# Dual_Motor_Driver.net
KiCad netlist of a schematic drawn in EAGLE
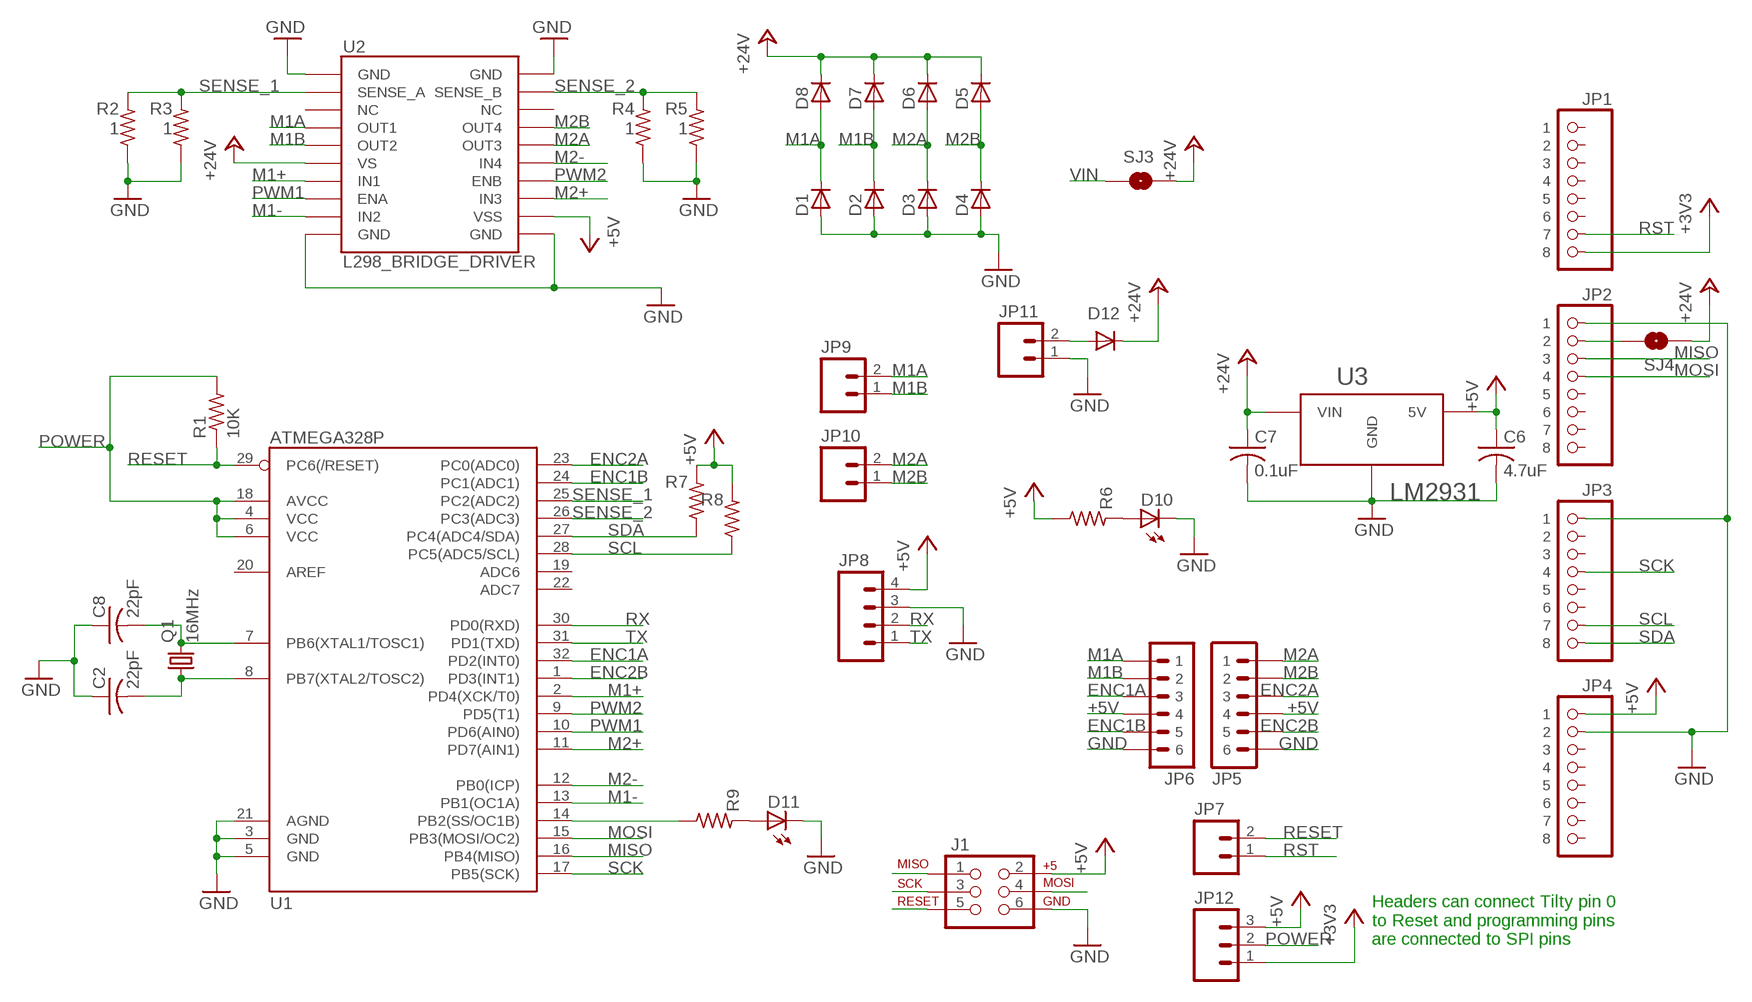
[diagram p0: schematic, sheet 1]

(export (version "E")
  (design (tool "Eeschema 10.0.6"))
  (components
    (comp (ref "C2")
      (value "22pF")
      (footprint "eagle-import:C0603")
      (libsource (lib "eagle-import") (part "C-USC0603"))
    )
    (comp (ref "C6")
      (value "4.7uF")
      (footprint "eagle-import:C0603")
      (libsource (lib "eagle-import") (part "C-USC0603"))
    )
    (comp (ref "C7")
      (value "0.1uF")
      (footprint "eagle-import:C0603")
      (libsource (lib "eagle-import") (part "C-USC0603"))
    )
    (comp (ref "C8")
      (value "22pF")
      (footprint "eagle-import:C0603")
      (libsource (lib "eagle-import") (part "C-USC0603"))
    )
    (comp (ref "D1")
      (value "D-SOD123")
      (footprint "eagle-import:SOD123")
      (fields (field (name "PART#") "CDBW140-G"))
      (libsource (lib "eagle-import") (part "D-SOD123"))
    )
    (comp (ref "D2")
      (value "D-SOD123")
      (footprint "eagle-import:SOD123")
      (fields (field (name "PART#") "CDBW140-G"))
      (libsource (lib "eagle-import") (part "D-SOD123"))
    )
    (comp (ref "D3")
      (value "D-SOD123")
      (footprint "eagle-import:SOD123")
      (fields (field (name "PART#") "CDBW140-G"))
      (libsource (lib "eagle-import") (part "D-SOD123"))
    )
    (comp (ref "D4")
      (value "D-SOD123")
      (footprint "eagle-import:SOD123")
      (fields (field (name "PART#") "CDBW140-G"))
      (libsource (lib "eagle-import") (part "D-SOD123"))
    )
    (comp (ref "D5")
      (value "D-SOD123")
      (footprint "eagle-import:SOD123")
      (fields (field (name "PART#") "CDBW140-G"))
      (libsource (lib "eagle-import") (part "D-SOD123"))
    )
    (comp (ref "D6")
      (value "D-SOD123")
      (footprint "eagle-import:SOD123")
      (fields (field (name "PART#") "CDBW140-G"))
      (libsource (lib "eagle-import") (part "D-SOD123"))
    )
    (comp (ref "D7")
      (value "D-SOD123")
      (footprint "eagle-import:SOD123")
      (fields (field (name "PART#") "CDBW140-G"))
      (libsource (lib "eagle-import") (part "D-SOD123"))
    )
    (comp (ref "D8")
      (value "D-SOD123")
      (footprint "eagle-import:SOD123")
      (fields (field (name "PART#") "CDBW140-G"))
      (libsource (lib "eagle-import") (part "D-SOD123"))
    )
    (comp (ref "D10")
      (value "LED-GREENLED-0805_NO_SILK")
      (footprint "eagle-import:LED-0805")
      (libsource (lib "eagle-import") (part "LED-GREENLED-0805_NO_SILK"))
    )
    (comp (ref "D11")
      (value "LED-GREENLED-0805_NO_SILK")
      (footprint "eagle-import:LED-0805")
      (libsource (lib "eagle-import") (part "LED-GREENLED-0805_NO_SILK"))
    )
    (comp (ref "D12")
      (value "DIODESMB")
      (footprint "eagle-import:SMB-DIODE")
      (libsource (lib "eagle-import") (part "DIODESMB"))
    )
    (comp (ref "J1")
      (value "AVR_SPI_PRG_62X3_LOCK")
      (footprint "eagle-import:2X3_LOCK")
      (libsource (lib "eagle-import") (part "AVR_SPI_PRG_62X3_LOCK"))
    )
    (comp (ref "JP1")
      (value "8-PIN_HEADER")
      (footprint "eagle-import:8-PIN_RECEPTACLE_LOCK_NO-SS")
      (libsource (lib "eagle-import") (part "8-PIN_HEADER"))
    )
    (comp (ref "JP2")
      (value "8-PIN_HEADER")
      (footprint "eagle-import:8-PIN_RECEPTACLE_LOCK_NO-SS")
      (libsource (lib "eagle-import") (part "8-PIN_HEADER"))
    )
    (comp (ref "JP3")
      (value "8-PIN_HEADER")
      (footprint "eagle-import:8-PIN_RECEPTACLE_LOCK_NO-SS")
      (libsource (lib "eagle-import") (part "8-PIN_HEADER"))
    )
    (comp (ref "JP4")
      (value "8-PIN_HEADER")
      (footprint "eagle-import:8-PIN_RECEPTACLE_LOCK_NO-SS")
      (libsource (lib "eagle-import") (part "8-PIN_HEADER"))
    )
    (comp (ref "JP5")
      (value "6PIN-SH_RIGHT_ANGLE")
      (footprint "eagle-import:6PIN-SH_SERIES_RA")
      (fields (field (name "PART#") "SM06B-SRSS-TB(LF)(SN)"))
      (libsource (lib "eagle-import") (part "6PIN-SH_RIGHT_ANGLE"))
    )
    (comp (ref "JP6")
      (value "6PIN-SH_RIGHT_ANGLE")
      (footprint "eagle-import:6PIN-SH_SERIES_RA")
      (fields (field (name "PART#") "SM06B-SRSS-TB(LF)(SN)"))
      (libsource (lib "eagle-import") (part "6PIN-SH_RIGHT_ANGLE"))
    )
    (comp (ref "JP7")
      (value "M02PTH")
      (footprint "eagle-import:1X02")
      (libsource (lib "eagle-import") (part "M02PTH"))
    )
    (comp (ref "JP8")
      (value "M04PTH")
      (footprint "eagle-import:1X04")
      (libsource (lib "eagle-import") (part "M04PTH"))
    )
    (comp (ref "JP9")
      (value "M02PTH")
      (footprint "eagle-import:1X02")
      (libsource (lib "eagle-import") (part "M02PTH"))
    )
    (comp (ref "JP10")
      (value "M02PTH")
      (footprint "eagle-import:1X02")
      (libsource (lib "eagle-import") (part "M02PTH"))
    )
    (comp (ref "JP11")
      (value "M02PTH")
      (footprint "eagle-import:1X02")
      (libsource (lib "eagle-import") (part "M02PTH"))
    )
    (comp (ref "JP12")
      (value "M03PTH")
      (footprint "eagle-import:1X03")
      (libsource (lib "eagle-import") (part "M03PTH"))
    )
    (comp (ref "Q1")
      (value "16MHz")
      (footprint "eagle-import:CTS406")
      (fields (field (name "PART#") "406C35D16M00000"))
      (libsource (lib "eagle-import") (part "CRYSTALCTS406"))
    )
    (comp (ref "R1")
      (value "10K")
      (footprint "eagle-import:R0603")
      (libsource (lib "eagle-import") (part "R-US_R0603"))
    )
    (comp (ref "R2")
      (value "1")
      (footprint "eagle-import:R0603")
      (libsource (lib "eagle-import") (part "R-US_R0603"))
    )
    (comp (ref "R3")
      (value "1")
      (footprint "eagle-import:R0603")
      (libsource (lib "eagle-import") (part "R-US_R0603"))
    )
    (comp (ref "R4")
      (value "1")
      (footprint "eagle-import:R0603")
      (libsource (lib "eagle-import") (part "R-US_R0603"))
    )
    (comp (ref "R5")
      (value "1")
      (footprint "eagle-import:R0603")
      (libsource (lib "eagle-import") (part "R-US_R0603"))
    )
    (comp (ref "R6")
      (value "R-US_R0603")
      (footprint "eagle-import:R0603")
      (libsource (lib "eagle-import") (part "R-US_R0603"))
    )
    (comp (ref "R7")
      (value "R-US_R0603")
      (footprint "eagle-import:R0603")
      (libsource (lib "eagle-import") (part "R-US_R0603"))
    )
    (comp (ref "R8")
      (value "R-US_R0603")
      (footprint "eagle-import:R0603")
      (libsource (lib "eagle-import") (part "R-US_R0603"))
    )
    (comp (ref "R9")
      (value "R-US_R0603")
      (footprint "eagle-import:R0603")
      (libsource (lib "eagle-import") (part "R-US_R0603"))
    )
    (comp (ref "SJ3")
      (value "SOLDERJUMPERNC")
      (footprint "eagle-import:SJ_2S")
      (libsource (lib "eagle-import") (part "SOLDERJUMPERNC"))
    )
    (comp (ref "SJ4")
      (value "SOLDERJUMPERTRACE")
      (footprint "eagle-import:SJ_2S-TRACE")
      (libsource (lib "eagle-import") (part "SOLDERJUMPERTRACE"))
    )
    (comp (ref "U1")
      (value "ATMEGA328P")
      (footprint "eagle-import:TQFP32-08")
      (libsource (lib "eagle-import") (part "ATMEGA328_SMT"))
    )
    (comp (ref "U2")
      (value "L298_BRIDGE_DRIVER")
      (footprint "eagle-import:POWERSO20")
      (libsource (lib "eagle-import") (part "L298_BRIDGE_DRIVER"))
    )
    (comp (ref "U3")
      (value "LM2931")
      (footprint "eagle-import:TO263")
      (libsource (lib "eagle-import") (part "LM2931"))
    )
  )
  (nets
    (net (code "1") (name "+3V3") (class "Default")
      (node (ref "JP1") (pin "P$8") (pinfunction "8_P$8") (pintype "passive"))
      (node (ref "JP12") (pin "1") (pinfunction "1_1") (pintype "passive"))
    )
    (net (code "2") (name "+5V") (class "Default")
      (node (ref "C6") (pin "1") (pinfunction "1_1") (pintype "passive"))
      (node (ref "J1") (pin "2") (pinfunction "2_2") (pintype "passive"))
      (node (ref "JP12") (pin "3") (pinfunction "3_3") (pintype "passive"))
      (node (ref "JP4") (pin "P$1") (pinfunction "1_P$1") (pintype "passive"))
      (node (ref "JP5") (pin "P$4") (pinfunction "4_P$4") (pintype "passive"))
      (node (ref "JP6") (pin "P$4") (pinfunction "4_P$4") (pintype "passive"))
      (node (ref "JP8") (pin "4") (pinfunction "4_4") (pintype "passive"))
      (node (ref "R6") (pin "1") (pinfunction "1_1") (pintype "passive"))
      (node (ref "R7") (pin "2") (pinfunction "2_2") (pintype "passive"))
      (node (ref "R8") (pin "2") (pinfunction "2_2") (pintype "passive"))
      (node (ref "U2") (pin "12") (pinfunction "VSS_12") (pintype "bidirectional"))
      (node (ref "U3") (pin "P$3") (pinfunction "5V_P$3") (pintype "bidirectional"))
    )
    (net (code "3") (name "+24V") (class "Default")
      (node (ref "C7") (pin "1") (pinfunction "1_1") (pintype "passive"))
      (node (ref "D12") (pin "C") (pinfunction "C_C") (pintype "passive"))
      (node (ref "D5") (pin "1") (pinfunction "C_1") (pintype "passive"))
      (node (ref "D6") (pin "1") (pinfunction "C_1") (pintype "passive"))
      (node (ref "D7") (pin "1") (pinfunction "C_1") (pintype "passive"))
      (node (ref "D8") (pin "1") (pinfunction "C_1") (pintype "passive"))
      (node (ref "SJ3") (pin "2") (pinfunction "2_2") (pintype "passive"))
      (node (ref "SJ4") (pin "1") (pinfunction "1_1") (pintype "passive"))
      (node (ref "U2") (pin "6") (pinfunction "VS_6") (pintype "bidirectional"))
      (node (ref "U3") (pin "P$2") (pinfunction "VIN_P$2") (pintype "bidirectional"))
    )
    (net (code "4") (name "/ENC1A") (class "Default")
      (node (ref "JP6") (pin "P$3") (pinfunction "3_P$3") (pintype "passive"))
      (node (ref "U1") (pin "32") (pinfunction "PD2(INT0)_32") (pintype "bidirectional"))
    )
    (net (code "5") (name "/ENC1B") (class "Default")
      (node (ref "JP6") (pin "P$5") (pinfunction "5_P$5") (pintype "passive"))
      (node (ref "U1") (pin "24") (pinfunction "PC1(ADC1)_24") (pintype "bidirectional"))
    )
    (net (code "6") (name "/ENC2A") (class "Default")
      (node (ref "JP5") (pin "P$3") (pinfunction "3_P$3") (pintype "passive"))
      (node (ref "U1") (pin "23") (pinfunction "PC0(ADC0)_23") (pintype "bidirectional"))
    )
    (net (code "7") (name "/ENC2B") (class "Default")
      (node (ref "JP5") (pin "P$5") (pinfunction "5_P$5") (pintype "passive"))
      (node (ref "U1") (pin "1") (pinfunction "PD3(INT1)_1") (pintype "bidirectional"))
    )
    (net (code "8") (name "/M1+") (class "Default")
      (node (ref "U1") (pin "2") (pinfunction "PD4(XCK/T0)_2") (pintype "bidirectional"))
      (node (ref "U2") (pin "7") (pinfunction "IN1_7") (pintype "bidirectional"))
    )
    (net (code "9") (name "/M1-") (class "Default")
      (node (ref "U1") (pin "13") (pinfunction "PB1(OC1A)_13") (pintype "bidirectional"))
      (node (ref "U2") (pin "9") (pinfunction "IN2_9") (pintype "bidirectional"))
    )
    (net (code "10") (name "/M1A") (class "Default")
      (node (ref "D1") (pin "1") (pinfunction "C_1") (pintype "passive"))
      (node (ref "D8") (pin "2") (pinfunction "A_2") (pintype "passive"))
      (node (ref "JP6") (pin "P$1") (pinfunction "1_P$1") (pintype "passive"))
      (node (ref "JP9") (pin "2") (pinfunction "2_2") (pintype "passive"))
      (node (ref "U2") (pin "4") (pinfunction "OUT1_4") (pintype "bidirectional"))
    )
    (net (code "11") (name "/M1B") (class "Default")
      (node (ref "D2") (pin "1") (pinfunction "C_1") (pintype "passive"))
      (node (ref "D7") (pin "2") (pinfunction "A_2") (pintype "passive"))
      (node (ref "JP6") (pin "P$2") (pinfunction "2_P$2") (pintype "passive"))
      (node (ref "JP9") (pin "1") (pinfunction "1_1") (pintype "passive"))
      (node (ref "U2") (pin "5") (pinfunction "OUT2_5") (pintype "bidirectional"))
    )
    (net (code "12") (name "/M2+") (class "Default")
      (node (ref "U1") (pin "11") (pinfunction "PD7(AIN1)_11") (pintype "bidirectional"))
      (node (ref "U2") (pin "13") (pinfunction "IN3_13") (pintype "bidirectional"))
    )
    (net (code "13") (name "/M2-") (class "Default")
      (node (ref "U1") (pin "12") (pinfunction "PB0(ICP)_12") (pintype "bidirectional"))
      (node (ref "U2") (pin "15") (pinfunction "IN4_15") (pintype "bidirectional"))
    )
    (net (code "14") (name "/M2A") (class "Default")
      (node (ref "D3") (pin "1") (pinfunction "C_1") (pintype "passive"))
      (node (ref "D6") (pin "2") (pinfunction "A_2") (pintype "passive"))
      (node (ref "JP10") (pin "2") (pinfunction "2_2") (pintype "passive"))
      (node (ref "JP5") (pin "P$1") (pinfunction "1_P$1") (pintype "passive"))
      (node (ref "U2") (pin "16") (pinfunction "OUT3_16") (pintype "bidirectional"))
    )
    (net (code "15") (name "/M2B") (class "Default")
      (node (ref "D4") (pin "1") (pinfunction "C_1") (pintype "passive"))
      (node (ref "D5") (pin "2") (pinfunction "A_2") (pintype "passive"))
      (node (ref "JP10") (pin "1") (pinfunction "1_1") (pintype "passive"))
      (node (ref "JP5") (pin "P$2") (pinfunction "2_P$2") (pintype "passive"))
      (node (ref "U2") (pin "17") (pinfunction "OUT4_17") (pintype "bidirectional"))
    )
    (net (code "16") (name "/MISO") (class "Default")
      (node (ref "J1") (pin "1") (pinfunction "1_1") (pintype "passive"))
      (node (ref "JP2") (pin "P$3") (pinfunction "3_P$3") (pintype "passive"))
      (node (ref "U1") (pin "16") (pinfunction "PB4(MISO)_16") (pintype "bidirectional"))
    )
    (net (code "17") (name "/MOSI") (class "Default")
      (node (ref "J1") (pin "4") (pinfunction "4_4") (pintype "passive"))
      (node (ref "JP2") (pin "P$4") (pinfunction "4_P$4") (pintype "passive"))
      (node (ref "U1") (pin "15") (pinfunction "PB3(MOSI/OC2)_15") (pintype "bidirectional"))
    )
    (net (code "18") (name "/POWER") (class "Default")
      (node (ref "JP12") (pin "2") (pinfunction "2_2") (pintype "passive"))
      (node (ref "R1") (pin "2") (pinfunction "2_2") (pintype "passive"))
      (node (ref "U1") (pin "18") (pinfunction "AVCC_18") (pintype "bidirectional"))
      (node (ref "U1") (pin "4") (pinfunction "VCC_4") (pintype "bidirectional"))
      (node (ref "U1") (pin "6") (pinfunction "VCC_6") (pintype "bidirectional"))
    )
    (net (code "19") (name "/PWM1") (class "Default")
      (node (ref "U1") (pin "10") (pinfunction "PD6(AIN0)_10") (pintype "bidirectional"))
      (node (ref "U2") (pin "8") (pinfunction "ENA_8") (pintype "bidirectional"))
    )
    (net (code "20") (name "/PWM2") (class "Default")
      (node (ref "U1") (pin "9") (pinfunction "PD5(T1)_9") (pintype "bidirectional"))
      (node (ref "U2") (pin "14") (pinfunction "ENB_14") (pintype "bidirectional"))
    )
    (net (code "21") (name "/RESET") (class "Default")
      (node (ref "J1") (pin "5") (pinfunction "5_5") (pintype "passive"))
      (node (ref "JP7") (pin "2") (pinfunction "2_2") (pintype "passive"))
      (node (ref "R1") (pin "1") (pinfunction "1_1") (pintype "passive"))
      (node (ref "U1") (pin "29") (pinfunction "PC6(/RESET)_29") (pintype "bidirectional"))
    )
    (net (code "22") (name "/RST") (class "Default")
      (node (ref "JP1") (pin "P$7") (pinfunction "7_P$7") (pintype "passive"))
      (node (ref "JP7") (pin "1") (pinfunction "1_1") (pintype "passive"))
    )
    (net (code "23") (name "/RX") (class "Default")
      (node (ref "JP8") (pin "2") (pinfunction "2_2") (pintype "passive"))
      (node (ref "U1") (pin "30") (pinfunction "PD0(RXD)_30") (pintype "bidirectional"))
    )
    (net (code "24") (name "/SCK") (class "Default")
      (node (ref "J1") (pin "3") (pinfunction "3_3") (pintype "passive"))
      (node (ref "JP3") (pin "P$4") (pinfunction "4_P$4") (pintype "passive"))
      (node (ref "U1") (pin "17") (pinfunction "PB5(SCK)_17") (pintype "bidirectional"))
    )
    (net (code "25") (name "/SCL") (class "Default")
      (node (ref "JP3") (pin "P$7") (pinfunction "7_P$7") (pintype "passive"))
      (node (ref "R8") (pin "1") (pinfunction "1_1") (pintype "passive"))
      (node (ref "U1") (pin "28") (pinfunction "PC5(ADC5/SCL)_28") (pintype "bidirectional"))
    )
    (net (code "26") (name "/SDA") (class "Default")
      (node (ref "JP3") (pin "P$8") (pinfunction "8_P$8") (pintype "passive"))
      (node (ref "R7") (pin "1") (pinfunction "1_1") (pintype "passive"))
      (node (ref "U1") (pin "27") (pinfunction "PC4(ADC4/SDA)_27") (pintype "bidirectional"))
    )
    (net (code "27") (name "/SENSE_1") (class "Default")
      (node (ref "R2") (pin "2") (pinfunction "2_2") (pintype "passive"))
      (node (ref "R3") (pin "2") (pinfunction "2_2") (pintype "passive"))
      (node (ref "U1") (pin "25") (pinfunction "PC2(ADC2)_25") (pintype "bidirectional"))
      (node (ref "U2") (pin "2") (pinfunction "SENSE_A_2") (pintype "bidirectional"))
    )
    (net (code "28") (name "/SENSE_2") (class "Default")
      (node (ref "R4") (pin "2") (pinfunction "2_2") (pintype "passive"))
      (node (ref "R5") (pin "2") (pinfunction "2_2") (pintype "passive"))
      (node (ref "U1") (pin "26") (pinfunction "PC3(ADC3)_26") (pintype "bidirectional"))
      (node (ref "U2") (pin "19") (pinfunction "SENSE_B_19") (pintype "bidirectional"))
    )
    (net (code "29") (name "/TX") (class "Default")
      (node (ref "JP8") (pin "1") (pinfunction "1_1") (pintype "passive"))
      (node (ref "U1") (pin "31") (pinfunction "PD1(TXD)_31") (pintype "bidirectional"))
    )
    (net (code "30") (name "/VIN") (class "Default")
      (node (ref "D12") (pin "A") (pinfunction "A_A") (pintype "passive"))
      (node (ref "JP11") (pin "2") (pinfunction "2_2") (pintype "passive"))
      (node (ref "SJ3") (pin "1") (pinfunction "1_1") (pintype "passive"))
    )
    (net (code "31") (name "GND") (class "Default")
      (node (ref "C2") (pin "1") (pinfunction "1_1") (pintype "passive"))
      (node (ref "C6") (pin "2") (pinfunction "2_2") (pintype "passive"))
      (node (ref "C7") (pin "2") (pinfunction "2_2") (pintype "passive"))
      (node (ref "C8") (pin "1") (pinfunction "1_1") (pintype "passive"))
      (node (ref "D1") (pin "2") (pinfunction "A_2") (pintype "passive"))
      (node (ref "D10") (pin "2") (pinfunction "C_2") (pintype "passive"))
      (node (ref "D11") (pin "2") (pinfunction "C_2") (pintype "passive"))
      (node (ref "D2") (pin "2") (pinfunction "A_2") (pintype "passive"))
      (node (ref "D3") (pin "2") (pinfunction "A_2") (pintype "passive"))
      (node (ref "D4") (pin "2") (pinfunction "A_2") (pintype "passive"))
      (node (ref "J1") (pin "6") (pinfunction "6_6") (pintype "passive"))
      (node (ref "JP11") (pin "1") (pinfunction "1_1") (pintype "passive"))
      (node (ref "JP2") (pin "P$1") (pinfunction "1_P$1") (pintype "passive"))
      (node (ref "JP3") (pin "P$1") (pinfunction "1_P$1") (pintype "passive"))
      (node (ref "JP4") (pin "P$2") (pinfunction "2_P$2") (pintype "passive"))
      (node (ref "JP5") (pin "P$6") (pinfunction "6_P$6") (pintype "passive"))
      (node (ref "JP6") (pin "P$6") (pinfunction "6_P$6") (pintype "passive"))
      (node (ref "JP8") (pin "3") (pinfunction "3_3") (pintype "passive"))
      (node (ref "R2") (pin "1") (pinfunction "1_1") (pintype "passive"))
      (node (ref "R3") (pin "1") (pinfunction "1_1") (pintype "passive"))
      (node (ref "R4") (pin "1") (pinfunction "1_1") (pintype "passive"))
      (node (ref "R5") (pin "1") (pinfunction "1_1") (pintype "passive"))
      (node (ref "U1") (pin "21") (pinfunction "AGND_21") (pintype "bidirectional"))
      (node (ref "U1") (pin "3") (pinfunction "GND_3") (pintype "bidirectional"))
      (node (ref "U1") (pin "5") (pinfunction "GND_5") (pintype "bidirectional"))
      (node (ref "U2") (pin "1") (pinfunction "GND_1") (pintype "bidirectional"))
      (node (ref "U2") (pin "10") (pinfunction "GND_10") (pintype "bidirectional"))
      (node (ref "U2") (pin "11") (pinfunction "GND_11") (pintype "bidirectional"))
      (node (ref "U2") (pin "20") (pinfunction "GND_20") (pintype "bidirectional"))
      (node (ref "U3") (pin "P$1") (pinfunction "GND_P$1") (pintype "bidirectional"))
    )
    (net (code "32") (name "Net-(D10-A)") (class "Default")
      (node (ref "D10") (pin "1") (pinfunction "A_1") (pintype "passive"))
      (node (ref "R6") (pin "2") (pinfunction "2_2") (pintype "passive"))
    )
    (net (code "33") (name "Net-(D11-A)") (class "Default")
      (node (ref "D11") (pin "1") (pinfunction "A_1") (pintype "passive"))
      (node (ref "R9") (pin "2") (pinfunction "2_2") (pintype "passive"))
    )
    (net (code "34") (name "Net-(JP2-2)") (class "Default")
      (node (ref "JP2") (pin "P$2") (pinfunction "2_P$2") (pintype "passive"))
      (node (ref "SJ4") (pin "2") (pinfunction "2_2") (pintype "passive"))
    )
    (net (code "35") (name "Net-(Q1-2)") (class "Default")
      (node (ref "C8") (pin "2") (pinfunction "2_2") (pintype "passive"))
      (node (ref "Q1") (pin "3") (pinfunction "2_3") (pintype "passive"))
      (node (ref "U1") (pin "7") (pinfunction "PB6(XTAL1/TOSC1)_7") (pintype "bidirectional"))
    )
    (net (code "36") (name "Net-(U1-PB2(SS{slash}OC1B))") (class "Default")
      (node (ref "R9") (pin "1") (pinfunction "1_1") (pintype "passive"))
      (node (ref "U1") (pin "14") (pinfunction "PB2(SS/OC1B)_14") (pintype "bidirectional"))
    )
    (net (code "37") (name "Net-(U1-PB7(XTAL2{slash}TOSC2))") (class "Default")
      (node (ref "C2") (pin "2") (pinfunction "2_2") (pintype "passive"))
      (node (ref "Q1") (pin "1") (pinfunction "1_1") (pintype "passive"))
      (node (ref "U1") (pin "8") (pinfunction "PB7(XTAL2/TOSC2)_8") (pintype "bidirectional"))
    )
    (net (code "38") (name "unconnected-(JP1-1-PadP$1)") (class "Default")
      (node (ref "JP1") (pin "P$1") (pinfunction "1_P$1") (pintype "passive"))
    )
    (net (code "39") (name "unconnected-(JP1-2-PadP$2)") (class "Default")
      (node (ref "JP1") (pin "P$2") (pinfunction "2_P$2") (pintype "passive"))
    )
    (net (code "40") (name "unconnected-(JP1-3-PadP$3)") (class "Default")
      (node (ref "JP1") (pin "P$3") (pinfunction "3_P$3") (pintype "passive"))
    )
    (net (code "41") (name "unconnected-(JP1-4-PadP$4)") (class "Default")
      (node (ref "JP1") (pin "P$4") (pinfunction "4_P$4") (pintype "passive"))
    )
    (net (code "42") (name "unconnected-(JP1-5-PadP$5)") (class "Default")
      (node (ref "JP1") (pin "P$5") (pinfunction "5_P$5") (pintype "passive"))
    )
    (net (code "43") (name "unconnected-(JP1-6-PadP$6)") (class "Default")
      (node (ref "JP1") (pin "P$6") (pinfunction "6_P$6") (pintype "passive"))
    )
    (net (code "44") (name "unconnected-(JP2-5-PadP$5)") (class "Default")
      (node (ref "JP2") (pin "P$5") (pinfunction "5_P$5") (pintype "passive"))
    )
    (net (code "45") (name "unconnected-(JP2-6-PadP$6)") (class "Default")
      (node (ref "JP2") (pin "P$6") (pinfunction "6_P$6") (pintype "passive"))
    )
    (net (code "46") (name "unconnected-(JP2-7-PadP$7)") (class "Default")
      (node (ref "JP2") (pin "P$7") (pinfunction "7_P$7") (pintype "passive"))
    )
    (net (code "47") (name "unconnected-(JP2-8-PadP$8)") (class "Default")
      (node (ref "JP2") (pin "P$8") (pinfunction "8_P$8") (pintype "passive"))
    )
    (net (code "48") (name "unconnected-(JP3-2-PadP$2)") (class "Default")
      (node (ref "JP3") (pin "P$2") (pinfunction "2_P$2") (pintype "passive"))
    )
    (net (code "49") (name "unconnected-(JP3-3-PadP$3)") (class "Default")
      (node (ref "JP3") (pin "P$3") (pinfunction "3_P$3") (pintype "passive"))
    )
    (net (code "50") (name "unconnected-(JP3-5-PadP$5)") (class "Default")
      (node (ref "JP3") (pin "P$5") (pinfunction "5_P$5") (pintype "passive"))
    )
    (net (code "51") (name "unconnected-(JP3-6-PadP$6)") (class "Default")
      (node (ref "JP3") (pin "P$6") (pinfunction "6_P$6") (pintype "passive"))
    )
    (net (code "52") (name "unconnected-(JP4-3-PadP$3)") (class "Default")
      (node (ref "JP4") (pin "P$3") (pinfunction "3_P$3") (pintype "passive"))
    )
    (net (code "53") (name "unconnected-(JP4-4-PadP$4)") (class "Default")
      (node (ref "JP4") (pin "P$4") (pinfunction "4_P$4") (pintype "passive"))
    )
    (net (code "54") (name "unconnected-(JP4-5-PadP$5)") (class "Default")
      (node (ref "JP4") (pin "P$5") (pinfunction "5_P$5") (pintype "passive"))
    )
    (net (code "55") (name "unconnected-(JP4-6-PadP$6)") (class "Default")
      (node (ref "JP4") (pin "P$6") (pinfunction "6_P$6") (pintype "passive"))
    )
    (net (code "56") (name "unconnected-(JP4-7-PadP$7)") (class "Default")
      (node (ref "JP4") (pin "P$7") (pinfunction "7_P$7") (pintype "passive"))
    )
    (net (code "57") (name "unconnected-(JP4-8-PadP$8)") (class "Default")
      (node (ref "JP4") (pin "P$8") (pinfunction "8_P$8") (pintype "passive"))
    )
    (net (code "58") (name "unconnected-(U1-ADC6-Pad19)") (class "Default")
      (node (ref "U1") (pin "19") (pinfunction "ADC6_19") (pintype "bidirectional"))
    )
    (net (code "59") (name "unconnected-(U1-ADC7-Pad22)") (class "Default")
      (node (ref "U1") (pin "22") (pinfunction "ADC7_22") (pintype "bidirectional"))
    )
    (net (code "60") (name "unconnected-(U1-AREF-Pad20)") (class "Default")
      (node (ref "U1") (pin "20") (pinfunction "AREF_20") (pintype "bidirectional"))
    )
    (net (code "61") (name "unconnected-(U2-NC-Pad3)") (class "Default")
      (node (ref "U2") (pin "3") (pinfunction "NC_3") (pintype "bidirectional"))
    )
    (net (code "62") (name "unconnected-(U2-NC-Pad18)") (class "Default")
      (node (ref "U2") (pin "18") (pinfunction "NC_18") (pintype "bidirectional"))
    )
  )
)
